# SCH_IoT_Weather_Station_With_Air_Quality.net
KiCad netlist of a schematic drawn in EasyEDA
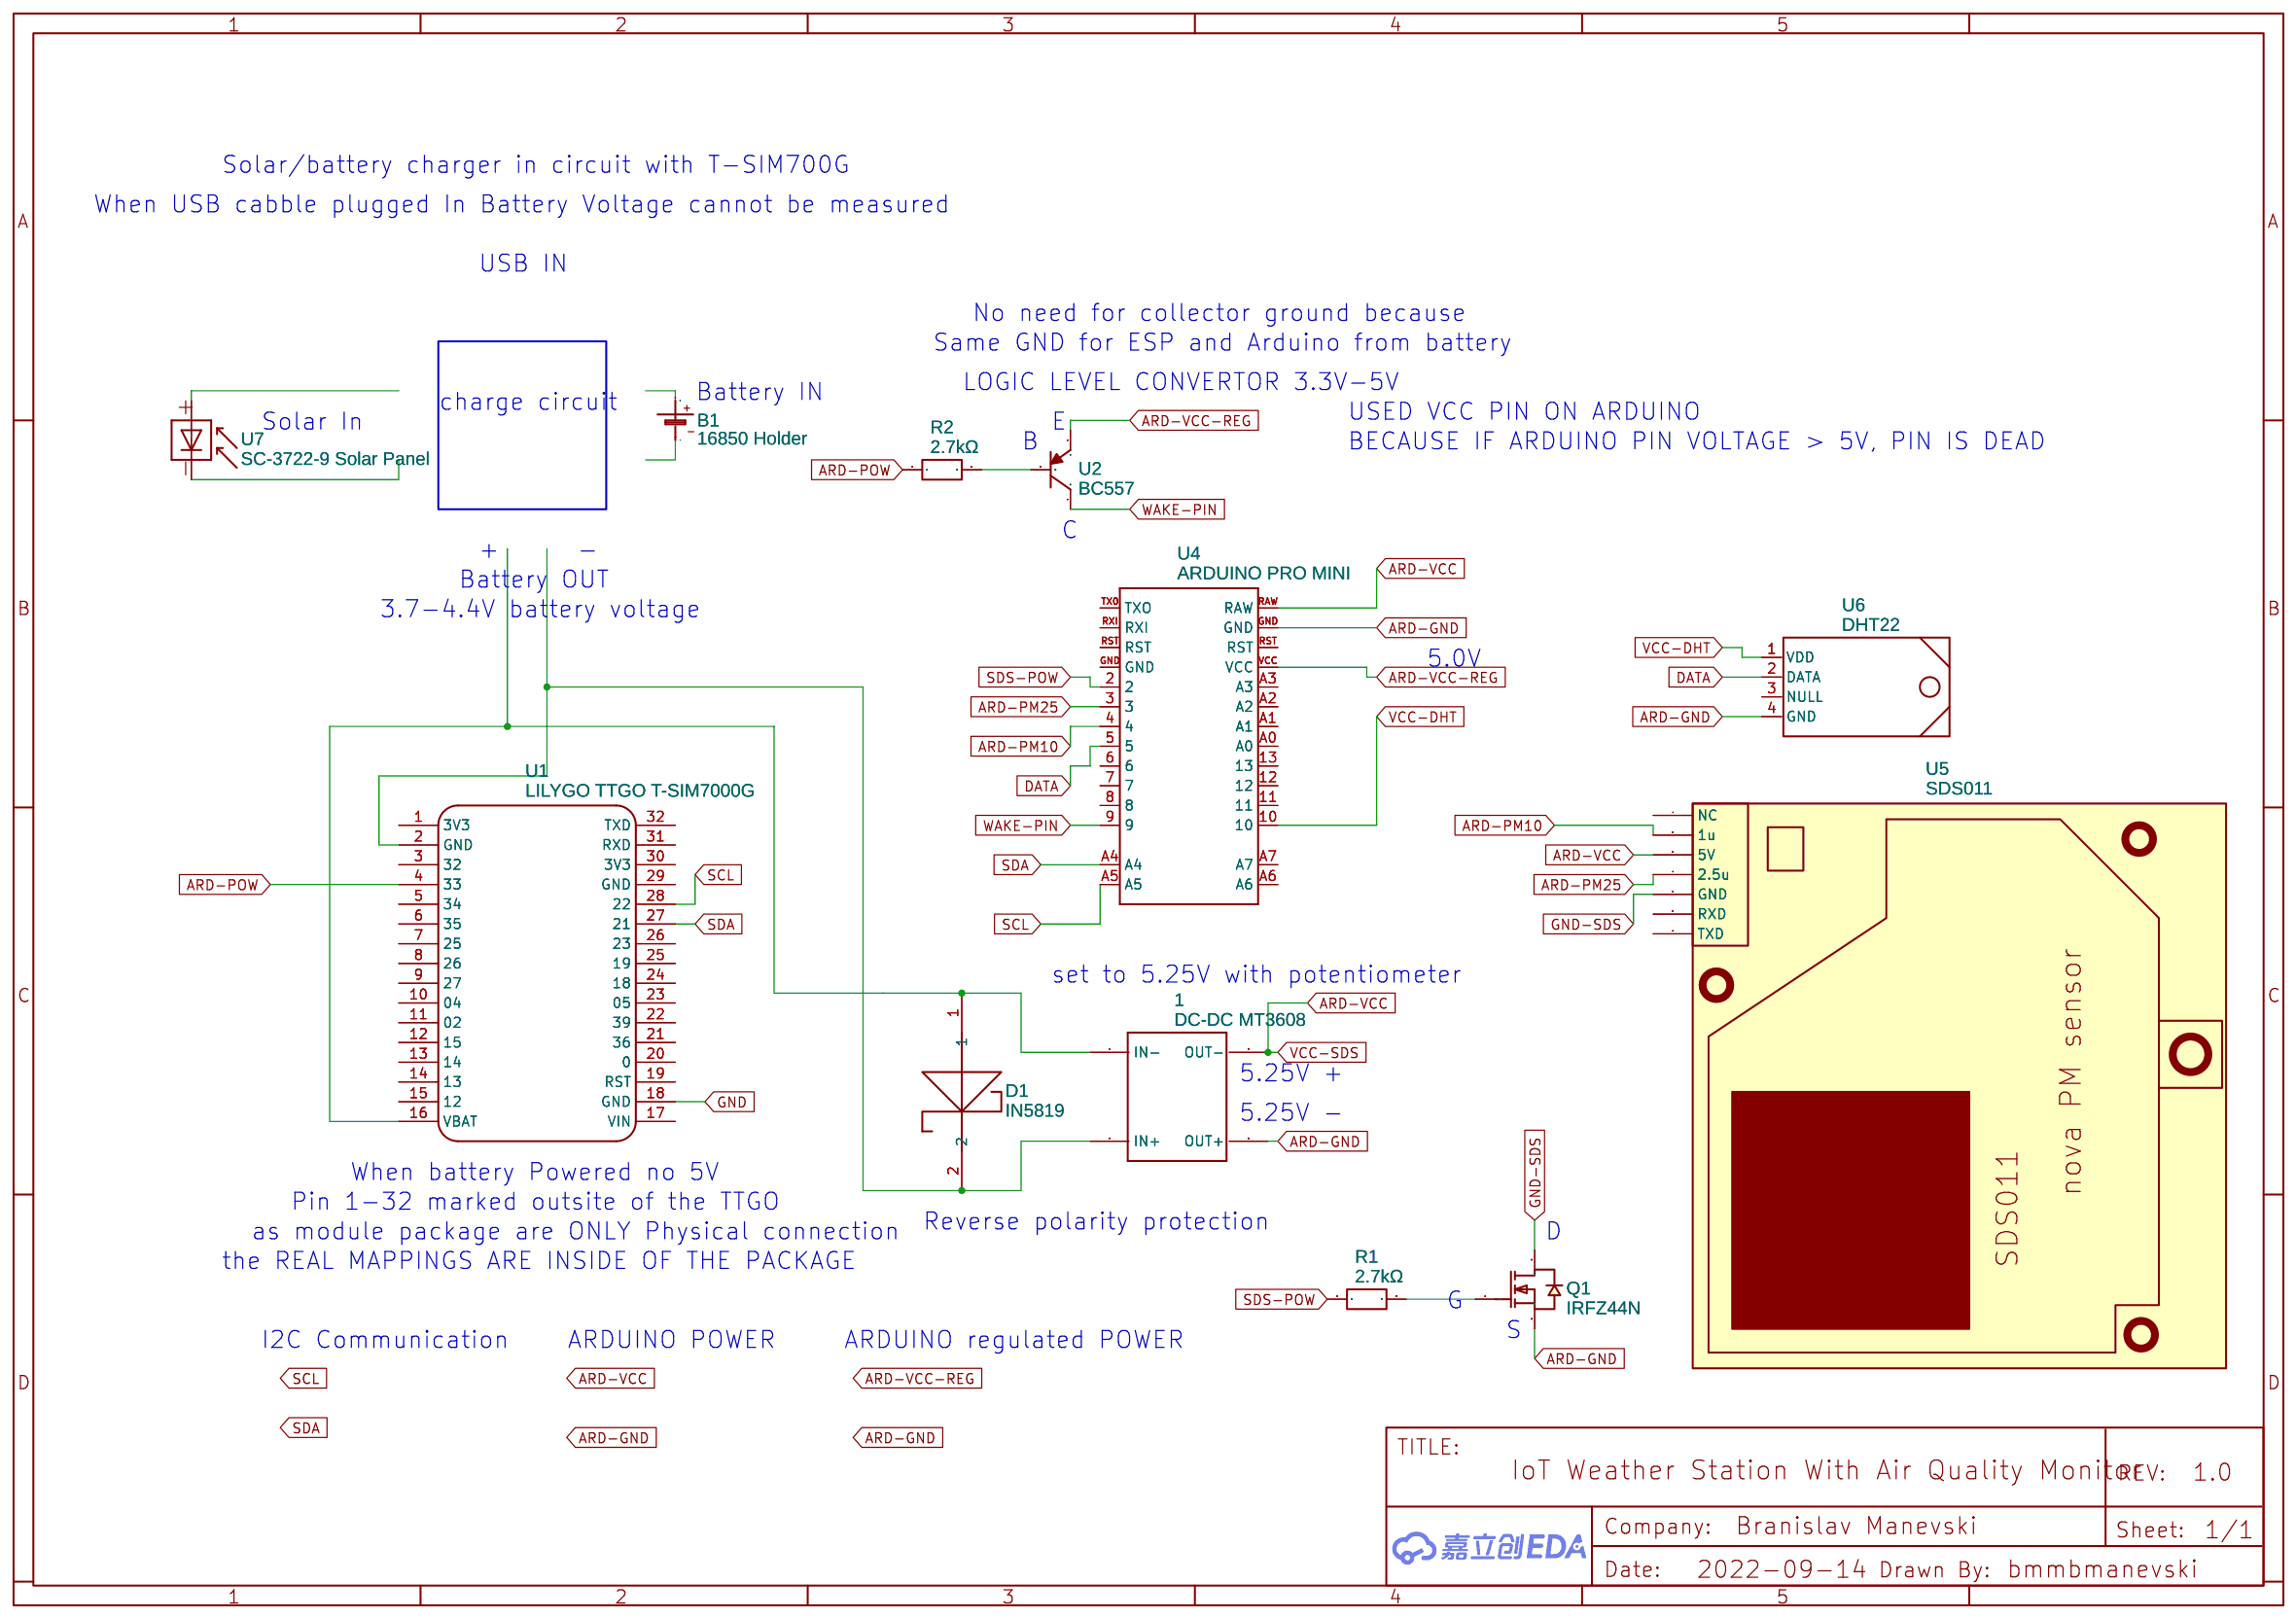
[diagram p0: schematic sheet]

(export (version "E")
  (design (tool "Eeschema 10.0.6"))
  (components
    (comp (ref "1") (value "DC-DC MT3608") (libsource (lib "") (part "DC-DC MT3608")))
    (comp (ref "B1") (value "16850 Holder") (libsource (lib "") (part "16850 Holder")))
    (comp (ref "D1")
      (value "IN5819")
      (fields
        (field (name "BOM_Manufacturer Part") "CDBA240LL-HF")
        (field (name "BOM_Supplier Part") "641-1698-1-ND")
      )
      (libsource (lib "") (part "IN5819"))
    )
    (comp (ref "Q1")
      (value "IRFZ44N")
      (fields (field (name "BOM_Manufacturer Part") "IRFZ44NPBF") (field (name "BOM_Supplier Part") "C2586"))
      (libsource (lib "") (part "IRFZ44N"))
    )
    (comp (ref "R1")
      (value "2.7kΩ")
      (fields
        (field (name "BOM_Manufacturer Part") "0402WGD2701TCE")
        (field (name "BOM_Supplier Part") "C423290")
      )
      (libsource (lib "") (part "0402WGD2701TCE"))
    )
    (comp (ref "R2")
      (value "2.7kΩ")
      (fields
        (field (name "BOM_Manufacturer Part") "0402WGD2701TCE")
        (field (name "BOM_Supplier Part") "C423290")
      )
      (libsource (lib "") (part "0402WGD2701TCE"))
    )
    (comp (ref "U1") (value "LILYGO TTGO T-SIM7000G") (libsource (lib "") (part "LILYGO TTGO T-SIM7000G")))
    (comp (ref "U2") (value "BC557") (libsource (lib "") (part "BC557")))
    (comp (ref "U4") (value "ARDUINO PRO MINI") (libsource (lib "") (part "ARDUINO PRO MINI")))
    (comp (ref "U5") (value "SDS011") (libsource (lib "") (part "SDS011")))
    (comp (ref "U6") (value "DHT22") (libsource (lib "") (part "DHT22")))
    (comp (ref "U7")
      (value "SC-3722-9 Solar Panel")
      (fields (field (name "BOM_Manufacturer Part") "SC-3722-9"))
      (libsource (lib "") (part "SC-3722-9 Solar Panel"))
    )
  )
  (nets
    (net (code "1") (name "ARD-GND") (class "Default")
      (node (ref "1") (pin "OUT+") (pinfunction "OUT+_OUT+") (pintype "unspecified"))
      (node (ref "Q1") (pin "3") (pinfunction "S_3") (pintype "unspecified"))
      (node (ref "U4") (pin "GND") (pinfunction "GND_GND") (pintype "unspecified"))
      (node (ref "U6") (pin "4") (pinfunction "GND_4") (pintype "unspecified"))
    )
    (net (code "2") (name "ARD-PM10") (class "Default")
      (node (ref "U4") (pin "4") (pinfunction "4_4") (pintype "unspecified"))
      (node (ref "U5") (pin "6") (pinfunction "1u_6") (pintype "unspecified"))
    )
    (net (code "3") (name "ARD-PM25") (class "Default")
      (node (ref "U4") (pin "3") (pinfunction "3_3") (pintype "unspecified"))
      (node (ref "U5") (pin "4") (pinfunction "2.5u_4") (pintype "unspecified"))
    )
    (net (code "4") (name "ARD-POW") (class "Default")
      (node (ref "R2") (pin "1") (pinfunction "1_1") (pintype "unspecified"))
      (node (ref "U1") (pin "4") (pinfunction "33_4") (pintype "unspecified"))
    )
    (net (code "5") (name "ARD-VCC") (class "Default")
      (node (ref "1") (pin "OUT-") (pinfunction "OUT-_OUT-") (pintype "unspecified"))
      (node (ref "U4") (pin "RAW") (pinfunction "RAW_RAW") (pintype "unspecified"))
      (node (ref "U5") (pin "5") (pinfunction "5V_5") (pintype "unspecified"))
    )
    (net (code "6") (name "ARD-VCC-REG") (class "Default")
      (node (ref "U2") (pin "3") (pinfunction "E_3") (pintype "unspecified"))
      (node (ref "U4") (pin "VCC") (pinfunction "VCC_VCC") (pintype "unspecified"))
    )
    (net (code "7") (name "DATA") (class "Default")
      (node (ref "U4") (pin "5") (pinfunction "5_5") (pintype "unspecified"))
      (node (ref "U6") (pin "2") (pinfunction "DATA_2") (pintype "unspecified"))
    )
    (net (code "8") (name "GND") (class "Default")
      (node (ref "U1") (pin "18") (pinfunction "GND_18") (pintype "unspecified"))
    )
    (net (code "9") (name "GND-SDS") (class "Default")
      (node (ref "Q1") (pin "2") (pinfunction "D_2") (pintype "unspecified"))
      (node (ref "U5") (pin "3") (pinfunction "GND_3") (pintype "unspecified"))
    )
    (net (code "10") (name "Net-(1-PadIN+)") (class "Default")
      (node (ref "1") (pin "IN+") (pinfunction "IN+_IN+") (pintype "unspecified"))
      (node (ref "D1") (pin "2") (pinfunction "2_2") (pintype "unspecified"))
      (node (ref "U1") (pin "2") (pinfunction "GND_2") (pintype "unspecified"))
    )
    (net (code "11") (name "Net-(Q1-G)") (class "Default")
      (node (ref "Q1") (pin "1") (pinfunction "G_1") (pintype "unspecified"))
      (node (ref "R1") (pin "2") (pinfunction "2_2") (pintype "unspecified"))
    )
    (net (code "12") (name "Net-(U1-VBAT)") (class "Default")
      (node (ref "1") (pin "IN-") (pinfunction "IN-_IN-") (pintype "unspecified"))
      (node (ref "D1") (pin "1") (pinfunction "1_1") (pintype "unspecified"))
      (node (ref "U1") (pin "16") (pinfunction "VBAT_16") (pintype "unspecified"))
    )
    (net (code "13") (name "Net-(U2-B)") (class "Default")
      (node (ref "R2") (pin "2") (pinfunction "2_2") (pintype "unspecified"))
      (node (ref "U2") (pin "2") (pinfunction "B_2") (pintype "unspecified"))
    )
    (net (code "14") (name "SCL") (class "Default")
      (node (ref "U1") (pin "28") (pinfunction "22_28") (pintype "unspecified"))
      (node (ref "U4") (pin "A5") (pinfunction "A5_A5") (pintype "unspecified"))
    )
    (net (code "15") (name "SDA") (class "Default")
      (node (ref "U1") (pin "27") (pinfunction "21_27") (pintype "unspecified"))
      (node (ref "U4") (pin "A4") (pinfunction "A4_A4") (pintype "unspecified"))
    )
    (net (code "16") (name "SDS-POW") (class "Default")
      (node (ref "R1") (pin "1") (pinfunction "1_1") (pintype "unspecified"))
      (node (ref "U4") (pin "2") (pinfunction "2_2") (pintype "unspecified"))
    )
    (net (code "17") (name "VCC-DHT") (class "Default")
      (node (ref "U4") (pin "10") (pinfunction "10_10") (pintype "unspecified"))
      (node (ref "U6") (pin "1") (pinfunction "VDD_1") (pintype "unspecified"))
    )
    (net (code "18") (name "WAKE-PIN") (class "Default")
      (node (ref "U2") (pin "1") (pinfunction "C_1") (pintype "unspecified"))
      (node (ref "U4") (pin "9") (pinfunction "9_9") (pintype "unspecified"))
    )
    (net (code "19") (name "unconnected-(B1-+-Pad1)") (class "Default")
      (node (ref "B1") (pin "1") (pinfunction "+_1") (pintype "bidirectional"))
    )
    (net (code "20") (name "unconnected-(B1---Pad2)") (class "Default")
      (node (ref "B1") (pin "2") (pinfunction "-_2") (pintype "bidirectional"))
    )
    (net (code "21") (name "unconnected-(U1-0-Pad20)") (class "Default")
      (node (ref "U1") (pin "20") (pinfunction "0_20") (pintype "unspecified"))
    )
    (net (code "22") (name "unconnected-(U1-02-Pad11)") (class "Default")
      (node (ref "U1") (pin "11") (pinfunction "02_11") (pintype "unspecified"))
    )
    (net (code "23") (name "unconnected-(U1-3V3-Pad1)") (class "Default")
      (node (ref "U1") (pin "1") (pinfunction "3V3_1") (pintype "unspecified"))
    )
    (net (code "24") (name "unconnected-(U1-3V3-Pad30)") (class "Default")
      (node (ref "U1") (pin "30") (pinfunction "3V3_30") (pintype "unspecified"))
    )
    (net (code "25") (name "unconnected-(U1-04-Pad10)") (class "Default")
      (node (ref "U1") (pin "10") (pinfunction "04_10") (pintype "unspecified"))
    )
    (net (code "26") (name "unconnected-(U1-05-Pad23)") (class "Default")
      (node (ref "U1") (pin "23") (pinfunction "05_23") (pintype "unspecified"))
    )
    (net (code "27") (name "unconnected-(U1-12-Pad15)") (class "Default")
      (node (ref "U1") (pin "15") (pinfunction "12_15") (pintype "unspecified"))
    )
    (net (code "28") (name "unconnected-(U1-13-Pad14)") (class "Default")
      (node (ref "U1") (pin "14") (pinfunction "13_14") (pintype "unspecified"))
    )
    (net (code "29") (name "unconnected-(U1-14-Pad13)") (class "Default")
      (node (ref "U1") (pin "13") (pinfunction "14_13") (pintype "unspecified"))
    )
    (net (code "30") (name "unconnected-(U1-15-Pad12)") (class "Default")
      (node (ref "U1") (pin "12") (pinfunction "15_12") (pintype "unspecified"))
    )
    (net (code "31") (name "unconnected-(U1-18-Pad24)") (class "Default")
      (node (ref "U1") (pin "24") (pinfunction "18_24") (pintype "unspecified"))
    )
    (net (code "32") (name "unconnected-(U1-19-Pad25)") (class "Default")
      (node (ref "U1") (pin "25") (pinfunction "19_25") (pintype "unspecified"))
    )
    (net (code "33") (name "unconnected-(U1-23-Pad26)") (class "Default")
      (node (ref "U1") (pin "26") (pinfunction "23_26") (pintype "unspecified"))
    )
    (net (code "34") (name "unconnected-(U1-25-Pad7)") (class "Default")
      (node (ref "U1") (pin "7") (pinfunction "25_7") (pintype "unspecified"))
    )
    (net (code "35") (name "unconnected-(U1-26-Pad8)") (class "Default")
      (node (ref "U1") (pin "8") (pinfunction "26_8") (pintype "unspecified"))
    )
    (net (code "36") (name "unconnected-(U1-27-Pad9)") (class "Default")
      (node (ref "U1") (pin "9") (pinfunction "27_9") (pintype "unspecified"))
    )
    (net (code "37") (name "unconnected-(U1-32-Pad3)") (class "Default")
      (node (ref "U1") (pin "3") (pinfunction "32_3") (pintype "unspecified"))
    )
    (net (code "38") (name "unconnected-(U1-34-Pad5)") (class "Default")
      (node (ref "U1") (pin "5") (pinfunction "34_5") (pintype "unspecified"))
    )
    (net (code "39") (name "unconnected-(U1-35-Pad6)") (class "Default")
      (node (ref "U1") (pin "6") (pinfunction "35_6") (pintype "unspecified"))
    )
    (net (code "40") (name "unconnected-(U1-36-Pad21)") (class "Default")
      (node (ref "U1") (pin "21") (pinfunction "36_21") (pintype "unspecified"))
    )
    (net (code "41") (name "unconnected-(U1-39-Pad22)") (class "Default")
      (node (ref "U1") (pin "22") (pinfunction "39_22") (pintype "unspecified"))
    )
    (net (code "42") (name "unconnected-(U1-GND-Pad29)") (class "Default")
      (node (ref "U1") (pin "29") (pinfunction "GND_29") (pintype "unspecified"))
    )
    (net (code "43") (name "unconnected-(U1-RST-Pad19)") (class "Default")
      (node (ref "U1") (pin "19") (pinfunction "RST_19") (pintype "unspecified"))
    )
    (net (code "44") (name "unconnected-(U1-RXD-Pad31)") (class "Default")
      (node (ref "U1") (pin "31") (pinfunction "RXD_31") (pintype "unspecified"))
    )
    (net (code "45") (name "unconnected-(U1-TXD-Pad32)") (class "Default")
      (node (ref "U1") (pin "32") (pinfunction "TXD_32") (pintype "unspecified"))
    )
    (net (code "46") (name "unconnected-(U1-VIN-Pad17)") (class "Default")
      (node (ref "U1") (pin "17") (pinfunction "VIN_17") (pintype "unspecified"))
    )
    (net (code "47") (name "unconnected-(U4-Pad6)") (class "Default")
      (node (ref "U4") (pin "6") (pinfunction "6_6") (pintype "unspecified"))
    )
    (net (code "48") (name "unconnected-(U4-Pad7)") (class "Default")
      (node (ref "U4") (pin "7") (pinfunction "7_7") (pintype "unspecified"))
    )
    (net (code "49") (name "unconnected-(U4-Pad8)") (class "Default")
      (node (ref "U4") (pin "8") (pinfunction "8_8") (pintype "unspecified"))
    )
    (net (code "50") (name "unconnected-(U4-Pad11)") (class "Default")
      (node (ref "U4") (pin "11") (pinfunction "11_11") (pintype "unspecified"))
    )
    (net (code "51") (name "unconnected-(U4-Pad12)") (class "Default")
      (node (ref "U4") (pin "12") (pinfunction "12_12") (pintype "unspecified"))
    )
    (net (code "52") (name "unconnected-(U4-Pad13)") (class "Default")
      (node (ref "U4") (pin "13") (pinfunction "13_13") (pintype "unspecified"))
    )
    (net (code "53") (name "unconnected-(U4-PadA0)") (class "Default")
      (node (ref "U4") (pin "A0") (pinfunction "A0_A0") (pintype "unspecified"))
    )
    (net (code "54") (name "unconnected-(U4-PadA1)") (class "Default")
      (node (ref "U4") (pin "A1") (pinfunction "A1_A1") (pintype "unspecified"))
    )
    (net (code "55") (name "unconnected-(U4-PadA2)") (class "Default")
      (node (ref "U4") (pin "A2") (pinfunction "A2_A2") (pintype "unspecified"))
    )
    (net (code "56") (name "unconnected-(U4-PadA3)") (class "Default")
      (node (ref "U4") (pin "A3") (pinfunction "A3_A3") (pintype "unspecified"))
    )
    (net (code "57") (name "unconnected-(U4-PadA6)") (class "Default")
      (node (ref "U4") (pin "A6") (pinfunction "A6_A6") (pintype "unspecified"))
    )
    (net (code "58") (name "unconnected-(U4-PadA7)") (class "Default")
      (node (ref "U4") (pin "A7") (pinfunction "A7_A7") (pintype "unspecified"))
    )
    (net (code "59") (name "unconnected-(U4-PadGND)") (class "Default")
      (node (ref "U4") (pin "GND") (pinfunction "GND_GND") (pintype "unspecified"))
    )
    (net (code "60") (name "unconnected-(U4-PadRST)") (class "Default")
      (node (ref "U4") (pin "RST") (pinfunction "RST_RST") (pintype "unspecified"))
    )
    (net (code "61") (name "unconnected-(U4-PadRST)_1") (class "Default")
      (node (ref "U4") (pin "RST") (pinfunction "RST_RST") (pintype "unspecified"))
    )
    (net (code "62") (name "unconnected-(U4-PadRXI)") (class "Default")
      (node (ref "U4") (pin "RXI") (pinfunction "RXI_RXI") (pintype "unspecified"))
    )
    (net (code "63") (name "unconnected-(U4-TXO-PadTX0)") (class "Default")
      (node (ref "U4") (pin "TX0") (pinfunction "TXO_TX0") (pintype "unspecified"))
    )
    (net (code "64") (name "unconnected-(U5-NC-Pad7)") (class "Default")
      (node (ref "U5") (pin "7") (pinfunction "NC_7") (pintype "unspecified"))
    )
    (net (code "65") (name "unconnected-(U5-RXD-Pad2)") (class "Default")
      (node (ref "U5") (pin "2") (pinfunction "RXD_2") (pintype "unspecified"))
    )
    (net (code "66") (name "unconnected-(U5-TXD-Pad1)") (class "Default")
      (node (ref "U5") (pin "1") (pinfunction "TXD_1") (pintype "unspecified"))
    )
    (net (code "67") (name "unconnected-(U6-NULL-Pad3)") (class "Default")
      (node (ref "U6") (pin "3") (pinfunction "NULL_3") (pintype "unspecified"))
    )
    (net (code "68") (name "unconnected-(U7-A-Pad+)") (class "Default")
      (node (ref "U7") (pin "+") (pinfunction "A_+") (pintype "unspecified"))
    )
    (net (code "69") (name "unconnected-(U7-C-Pad-)") (class "Default")
      (node (ref "U7") (pin "-") (pinfunction "C_-") (pintype "unspecified"))
    )
  )
)
